# ESP_MainChip.net
KiCad netlist of a schematic drawn in Altium Designer
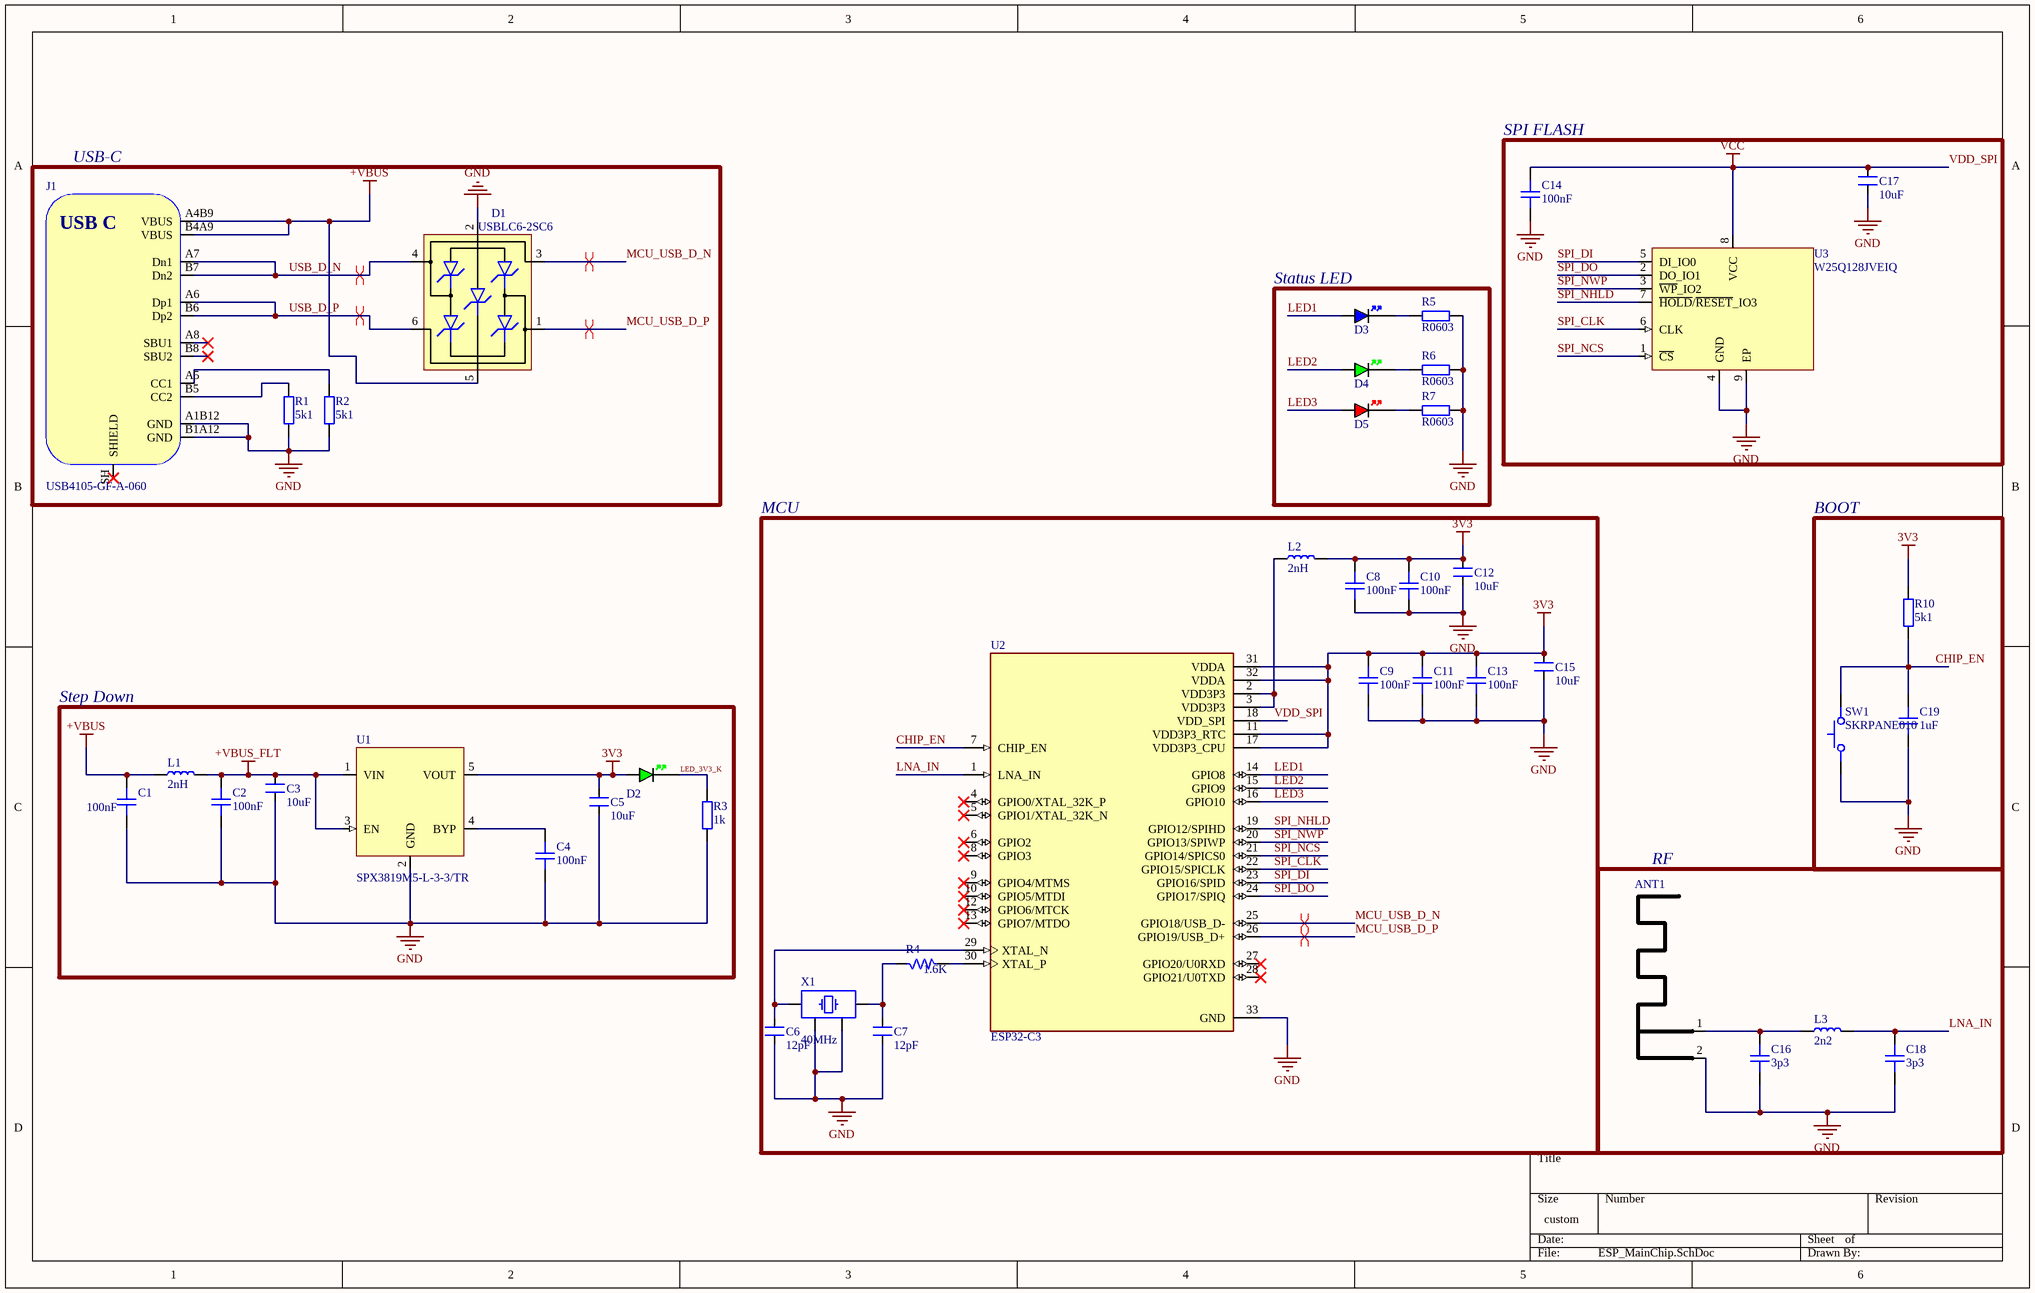
[diagram p0: ESP_MainChip.SchDoc]

(export (version "E")
  (design (tool "Eeschema 10.0.6"))
  (components
    (comp (ref "ANT1")
      (value "PCB Antenna 2.4GHz 50Ohm")
      (footprint "ANT_IFA_USB_2_4GHZ_50R")
      (description "Inverted F 2.4GHz ISM PCB Antenna 50 Ohm")
      (libsource (lib "PMS67") (part "ANT_IFA_USB_2_4GHZ_50R"))
    )
    (comp (ref "C1")
      (value "100nF")
      (footprint "CAP_0603")
      (description "Capacitor SMD 0603")
      (libsource (lib "PMS67") (part "CAP_0603"))
    )
    (comp (ref "C2")
      (value "100nF")
      (footprint "CAP_0603")
      (description "Capacitor SMD 0603")
      (libsource (lib "PMS67") (part "CAP_0603"))
    )
    (comp (ref "C3")
      (value "10uF")
      (footprint "CAP_1206")
      (description "10µF ±10% 50V Ceramic Capacitor X7R 1206 (3216 Metric)")
      (fields
        (field (name "MANUFACTURER") "KEMET")
        (field (name "MANUFACTURER PART NUMBER") "CL31B106KBHNNNE")
      )
      (libsource (lib "ESTEEMPCBLIB") (part "CAP_10uF-50V-10%-1206"))
    )
    (comp (ref "C4")
      (value "100nF")
      (footprint "CAP_0603")
      (description "Capacitor SMD 0603")
      (libsource (lib "PMS67") (part "CAP_0603"))
    )
    (comp (ref "C5")
      (value "10uF")
      (footprint "CAP_1206")
      (description "10µF ±10% 50V Ceramic Capacitor X7R 1206 (3216 Metric)")
      (fields
        (field (name "MANUFACTURER") "KEMET")
        (field (name "MANUFACTURER PART NUMBER") "CL31B106KBHNNNE")
      )
      (libsource (lib "ESTEEMPCBLIB") (part "CAP_10uF-50V-10%-1206"))
    )
    (comp (ref "C6")
      (value "12pF")
      (footprint "CAP_0805")
      (description "12pF ±5% 50V Ceramic Capacitor C0G, NP0 0805 (2012 Metric)")
      (fields
        (field (name "MANUFACTURER") "KEMET")
        (field (name "MANUFACTURER PART NUMBER") "CC0805JRNPO9BN120")
      )
      (libsource (lib "ESTEEMPCBLIB") (part "CAP_12pF-50V-5%-0805"))
    )
    (comp (ref "C7")
      (value "12pF")
      (footprint "CAP_0805")
      (description "12pF ±5% 50V Ceramic Capacitor C0G, NP0 0805 (2012 Metric)")
      (fields
        (field (name "MANUFACTURER") "KEMET")
        (field (name "MANUFACTURER PART NUMBER") "CC0805JRNPO9BN120")
      )
      (libsource (lib "ESTEEMPCBLIB") (part "CAP_12pF-50V-5%-0805"))
    )
    (comp (ref "C8")
      (value "100nF")
      (footprint "CAP_0603")
      (description "Capacitor SMD 0603")
      (libsource (lib "PMS67") (part "CAP_0603"))
    )
    (comp (ref "C9")
      (value "100nF")
      (footprint "CAP_0603")
      (description "Capacitor SMD 0603")
      (libsource (lib "PMS67") (part "CAP_0603"))
    )
    (comp (ref "C10")
      (value "100nF")
      (footprint "CAP_0603")
      (description "Capacitor SMD 0603")
      (libsource (lib "PMS67") (part "CAP_0603"))
    )
    (comp (ref "C11")
      (value "100nF")
      (footprint "CAP_0603")
      (description "Capacitor SMD 0603")
      (libsource (lib "PMS67") (part "CAP_0603"))
    )
    (comp (ref "C12")
      (value "10uF")
      (footprint "CAP_1206")
      (description "10µF ±10% 50V Ceramic Capacitor X7R 1206 (3216 Metric)")
      (fields
        (field (name "MANUFACTURER") "KEMET")
        (field (name "MANUFACTURER PART NUMBER") "CL31B106KBHNNNE")
      )
      (libsource (lib "ESTEEMPCBLIB") (part "CAP_10uF-50V-10%-1206"))
    )
    (comp (ref "C13")
      (value "100nF")
      (footprint "CAP_0603")
      (description "Capacitor SMD 0603")
      (libsource (lib "PMS67") (part "CAP_0603"))
    )
    (comp (ref "C14")
      (value "100nF")
      (footprint "CAP_0603")
      (description "Capacitor SMD 0603")
      (libsource (lib "PMS67") (part "CAP_0603"))
    )
    (comp (ref "C15")
      (value "10uF")
      (footprint "CAP_1206")
      (description "10µF ±10% 50V Ceramic Capacitor X7R 1206 (3216 Metric)")
      (fields
        (field (name "MANUFACTURER") "KEMET")
        (field (name "MANUFACTURER PART NUMBER") "CL31B106KBHNNNE")
      )
      (libsource (lib "ESTEEMPCBLIB") (part "CAP_10uF-50V-10%-1206"))
    )
    (comp (ref "C16")
      (value "3p3")
      (footprint "CAP_0201")
      (description "Capacitor SMD 0201")
      (libsource (lib "PMS67") (part "CAP_0201"))
    )
    (comp (ref "C17")
      (value "10uF")
      (footprint "CAP_1206")
      (description "10µF ±10% 50V Ceramic Capacitor X7R 1206 (3216 Metric)")
      (fields
        (field (name "MANUFACTURER") "KEMET")
        (field (name "MANUFACTURER PART NUMBER") "CL31B106KBHNNNE")
      )
      (libsource (lib "ESTEEMPCBLIB") (part "CAP_10uF-50V-10%-1206"))
    )
    (comp (ref "C18")
      (value "3p3")
      (footprint "CAP_0201")
      (description "Capacitor SMD 0201")
      (libsource (lib "PMS67") (part "CAP_0201"))
    )
    (comp (ref "C19")
      (value "1uF")
      (footprint "CAP_0603")
      (description "Capacitor SMD 0603")
      (libsource (lib "PMS67") (part "CAP_0603"))
    )
    (comp (ref "D1")
      (value "USBLC6-2SC6")
      (footprint "SOT-23-6")
      (description "Low-Capacitance ESD Protection USB")
      (fields (field (name "MANUFACTURER") "STMicroelectronics"))
      (libsource (lib "PMS67") (part "USBLC6-2SC6"))
    )
    (comp (ref "D2")
      (value "GREEN")
      (footprint "LED_0402_GREEN")
      (description "LED 0402 GREEN SMD")
      (libsource (lib "PMS67") (part "LED_0402_GREEN"))
    )
    (comp (ref "D3")
      (value "BLUE")
      (footprint "LED_0402_BLUE")
      (description "LED 0402 BLUE SMD")
      (libsource (lib "PMS67") (part "LED_0402_BLUE"))
    )
    (comp (ref "D4")
      (value "GREEN")
      (footprint "LED_0402_GREEN")
      (description "LED 0402 GREEN SMD")
      (libsource (lib "PMS67") (part "LED_0402_GREEN"))
    )
    (comp (ref "D5")
      (value "RED")
      (footprint "LED_0402_RED")
      (description "LED 0402 RED SMD")
      (libsource (lib "PMS67") (part "LED_0402_RED"))
    )
    (comp (ref "J1")
      (value "USB4105-GF-A-060")
      (footprint "USB4105-GF-A-060")
      (description "USB Connector Type C SMT 12 Pin")
      (fields (field (name "MANUFACTURER") "GCT"))
      (libsource (lib "PMS67") (part "USB4105-GF-A-060"))
    )
    (comp (ref "L1")
      (value "2nH")
      (footprint "IND_0603")
      (description "Inductor SMD 0603")
      (libsource (lib "PMS67") (part "IND_0603"))
    )
    (comp (ref "L2")
      (value "2nH")
      (footprint "IND_0603")
      (description "Inductor SMD 0603")
      (libsource (lib "PMS67") (part "IND_0603"))
    )
    (comp (ref "L3")
      (value "2n2")
      (footprint "IND_1008")
      (description "Inductor SMD 1008")
      (libsource (lib "PMS67") (part "IND_1008"))
    )
    (comp (ref "R1")
      (value "5k1")
      (footprint "RES_0805")
      (description "Resistor SMD 0805")
      (libsource (lib "PMS67") (part "RES_0805"))
    )
    (comp (ref "R2")
      (value "5k1")
      (footprint "RES_0805")
      (description "Resistor SMD 0805")
      (libsource (lib "PMS67") (part "RES_0805"))
    )
    (comp (ref "R3")
      (value "1k")
      (footprint "RES_0603")
      (description "Resistor SMD 0603")
      (libsource (lib "PMS67") (part "RES_0603"))
    )
    (comp (ref "R4")
      (value "1.6K")
      (footprint "RES_0603")
      (description "1.6 kOhms ±1% 0.1W, 1/10W Chip Resistor 0603 (1608 Metric) Thin Film")
      (fields (field (name "MANUFACTURER") "NA"))
      (libsource (lib "ESTEEMPCBLIB") (part "RES_1.6K-0.1W-1%-0603"))
    )
    (comp (ref "R5")
      (value "R0603")
      (footprint "RES_0603")
      (description "Resistor SMD 0603")
      (libsource (lib "PMS67") (part "RES_0603"))
    )
    (comp (ref "R6")
      (value "R0603")
      (footprint "RES_0603")
      (description "Resistor SMD 0603")
      (libsource (lib "PMS67") (part "RES_0603"))
    )
    (comp (ref "R7")
      (value "R0603")
      (footprint "RES_0603")
      (description "Resistor SMD 0603")
      (libsource (lib "PMS67") (part "RES_0603"))
    )
    (comp (ref "R10")
      (value "5k1")
      (footprint "RES_0805")
      (description "Resistor SMD 0805")
      (libsource (lib "PMS67") (part "RES_0805"))
    )
    (comp (ref "SW1")
      (value "SKRPANE010")
      (footprint "SKRPANE010")
      (description "Tactile Switch SMD SPST")
      (fields (field (name "MANUFACTURER") "Alps Alpine"))
      (libsource (lib "PMS67") (part "SKRPANE010"))
    )
    (comp (ref "U1")
      (value "SPX3819M5-L-3-3/TR")
      (footprint "SOT-23-5")
      (description "500mA +3.3V Low-Noise LDO Voltage Regulator")
      (fields (field (name "MANUFACTURER") "MaxLinear"))
      (libsource (lib "PMS67") (part "SPX3819M5-L-3-3/TR"))
    )
    (comp (ref "U2")
      (value "ESP32-C3")
      (footprint "QFN50P500X500X90-33N")
      (fields (field (name "MF") "{'manufacturer': u'Espressif Systems'}"))
      (libsource (lib "SnapEDA_Library") (part "ESP32-C3"))
    )
    (comp (ref "U3")
      (value "W25Q128JVEIQ")
      (footprint "WSON-8-8X6")
      (description "3V 128M-BIT SERIAL FLASH MEMORY WITH DUAL/QUAD SPI & QPI & DTR WSON-8")
      (fields (field (name "MANUFACTURER") "Winbond"))
      (libsource (lib "PMS67") (part "W25Q128JVEIQ"))
    )
    (comp (ref "X1")
      (value "40MHz")
      (footprint "XTAL_2016")
      (description "Crystal SMD 4-Pin 2.0x1.6mm")
      (libsource (lib "PMS67") (part "XTAL_2016"))
    )
  )
  (nets
    (net (code "1") (name "+VBUS") (class "Default")
      (node (ref "C1") (pin "2") (pinfunction "2_2") (pintype "passive"))
      (node (ref "D1") (pin "5") (pinfunction "VBUS_5") (pintype "power_in"))
      (node (ref "J1") (pin "A4B9") (pinfunction "VBUS_A4B9") (pintype "passive"))
      (node (ref "J1") (pin "B4A9") (pinfunction "VBUS_B4A9") (pintype "passive"))
      (node (ref "L1") (pin "1") (pinfunction "1_1") (pintype "passive"))
    )
    (net (code "2") (name "+VBUS_FLT") (class "Default")
      (node (ref "C2") (pin "2") (pinfunction "2_2") (pintype "passive"))
      (node (ref "C3") (pin "2") (pinfunction "2_2") (pintype "passive"))
      (node (ref "L1") (pin "2") (pinfunction "2_2") (pintype "passive"))
      (node (ref "U1") (pin "1") (pinfunction "VIN_1") (pintype "power_in"))
      (node (ref "U1") (pin "3") (pinfunction "EN_3") (pintype "input"))
    )
    (net (code "3") (name "/CHIP_EN") (class "Default")
      (node (ref "C19") (pin "2") (pinfunction "2_2") (pintype "passive"))
      (node (ref "R10") (pin "1") (pinfunction "1_1") (pintype "passive"))
      (node (ref "SW1") (pin "34") (pintype "passive"))
      (node (ref "U2") (pin "7") (pinfunction "CHIP_EN_7") (pintype "input"))
    )
    (net (code "4") (name "/LED1") (class "Default")
      (node (ref "D3") (pin "A") (pinfunction "A_A") (pintype "passive"))
      (node (ref "U2") (pin "14") (pinfunction "GPIO8_14") (pintype "bidirectional"))
    )
    (net (code "5") (name "/LED2") (class "Default")
      (node (ref "D4") (pin "A") (pinfunction "A_A") (pintype "passive"))
      (node (ref "U2") (pin "15") (pinfunction "GPIO9_15") (pintype "bidirectional"))
    )
    (net (code "6") (name "/LED3") (class "Default")
      (node (ref "D5") (pin "A") (pinfunction "A_A") (pintype "passive"))
      (node (ref "U2") (pin "16") (pinfunction "GPIO10_16") (pintype "bidirectional"))
    )
    (net (code "7") (name "/LED_3V3_K") (class "Default")
      (node (ref "D2") (pin "K") (pinfunction "K_K") (pintype "passive"))
      (node (ref "R3") (pin "2") (pinfunction "2_2") (pintype "passive"))
    )
    (net (code "8") (name "/LNA_IN") (class "Default")
      (node (ref "C18") (pin "2") (pinfunction "2_2") (pintype "passive"))
      (node (ref "L3") (pin "2") (pinfunction "2_2") (pintype "passive"))
      (node (ref "U2") (pin "1") (pinfunction "LNA_IN_1") (pintype "input"))
    )
    (net (code "9") (name "/MCU_USB_D_N") (class "Default")
      (node (ref "D1") (pin "3") (pinfunction "IO2_3") (pintype "bidirectional"))
      (node (ref "U2") (pin "25") (pinfunction "GPIO18/USB_D-_25") (pintype "bidirectional"))
    )
    (net (code "10") (name "/MCU_USB_D_P") (class "Default")
      (node (ref "D1") (pin "1") (pinfunction "IO1_1") (pintype "bidirectional"))
      (node (ref "U2") (pin "26") (pinfunction "GPIO19/USB_D+_26") (pintype "bidirectional"))
    )
    (net (code "11") (name "/SPI_CLK") (class "Default")
      (node (ref "U2") (pin "22") (pinfunction "GPIO15/SPICLK_22") (pintype "bidirectional"))
      (node (ref "U3") (pin "6") (pinfunction "CLK_6") (pintype "input"))
    )
    (net (code "12") (name "/SPI_DI") (class "Default")
      (node (ref "U2") (pin "23") (pinfunction "GPIO16/SPID_23") (pintype "bidirectional"))
      (node (ref "U3") (pin "5") (pinfunction "DI_IO0_5") (pintype "bidirectional"))
    )
    (net (code "13") (name "/SPI_DO") (class "Default")
      (node (ref "U2") (pin "24") (pinfunction "GPIO17/SPIQ_24") (pintype "bidirectional"))
      (node (ref "U3") (pin "2") (pinfunction "DO_IO1_2") (pintype "bidirectional"))
    )
    (net (code "14") (name "/SPI_NCS") (class "Default")
      (node (ref "U2") (pin "21") (pinfunction "GPIO14/SPICS0_21") (pintype "bidirectional"))
      (node (ref "U3") (pin "1") (pinfunction "~{CS}_1") (pintype "input"))
    )
    (net (code "15") (name "/SPI_NHLD") (class "Default")
      (node (ref "U2") (pin "19") (pinfunction "GPIO12/SPIHD_19") (pintype "bidirectional"))
      (node (ref "U3") (pin "7") (pinfunction "~{HOLD}/~{RESET}_IO3_7") (pintype "bidirectional"))
    )
    (net (code "16") (name "/SPI_NWP") (class "Default")
      (node (ref "U2") (pin "20") (pinfunction "GPIO13/SPIWP_20") (pintype "bidirectional"))
      (node (ref "U3") (pin "3") (pinfunction "~{WP}_IO2_3") (pintype "bidirectional"))
    )
    (net (code "17") (name "/USB_D_N") (class "Default")
      (node (ref "D1") (pin "4") (pinfunction "IO2_4") (pintype "bidirectional"))
      (node (ref "J1") (pin "A7") (pinfunction "Dn1_A7") (pintype "passive"))
      (node (ref "J1") (pin "B7") (pinfunction "Dn2_B7") (pintype "passive"))
    )
    (net (code "18") (name "/USB_D_P") (class "Default")
      (node (ref "D1") (pin "6") (pinfunction "IO1_6") (pintype "bidirectional"))
      (node (ref "J1") (pin "A6") (pinfunction "Dp1_A6") (pintype "passive"))
      (node (ref "J1") (pin "B6") (pinfunction "Dp2_B6") (pintype "passive"))
    )
    (net (code "19") (name "3V3") (class "Default")
      (node (ref "C10") (pin "2") (pinfunction "2_2") (pintype "passive"))
      (node (ref "C11") (pin "2") (pinfunction "2_2") (pintype "passive"))
      (node (ref "C12") (pin "2") (pinfunction "2_2") (pintype "passive"))
      (node (ref "C13") (pin "2") (pinfunction "2_2") (pintype "passive"))
      (node (ref "C15") (pin "2") (pinfunction "2_2") (pintype "passive"))
      (node (ref "C5") (pin "2") (pinfunction "2_2") (pintype "passive"))
      (node (ref "C8") (pin "2") (pinfunction "2_2") (pintype "passive"))
      (node (ref "C9") (pin "2") (pinfunction "2_2") (pintype "passive"))
      (node (ref "D2") (pin "A") (pinfunction "A_A") (pintype "passive"))
      (node (ref "L2") (pin "2") (pinfunction "2_2") (pintype "passive"))
      (node (ref "R10") (pin "2") (pinfunction "2_2") (pintype "passive"))
      (node (ref "U1") (pin "5") (pinfunction "VOUT_5") (pintype "power_in"))
      (node (ref "U2") (pin "11") (pinfunction "VDD3P3_RTC_11") (pintype "power_in"))
      (node (ref "U2") (pin "17") (pinfunction "VDD3P3_CPU_17") (pintype "power_in"))
      (node (ref "U2") (pin "31") (pinfunction "VDDA_31") (pintype "power_in"))
      (node (ref "U2") (pin "32") (pinfunction "VDDA_32") (pintype "power_in"))
    )
    (net (code "20") (name "GND") (class "Default")
      (node (ref "ANT1") (pin "2") (pinfunction "GND_2") (pintype "passive"))
      (node (ref "C1") (pin "1") (pinfunction "1_1") (pintype "passive"))
      (node (ref "C10") (pin "1") (pinfunction "1_1") (pintype "passive"))
      (node (ref "C11") (pin "1") (pinfunction "1_1") (pintype "passive"))
      (node (ref "C12") (pin "1") (pinfunction "1_1") (pintype "passive"))
      (node (ref "C13") (pin "1") (pinfunction "1_1") (pintype "passive"))
      (node (ref "C14") (pin "1") (pinfunction "1_1") (pintype "passive"))
      (node (ref "C15") (pin "1") (pinfunction "1_1") (pintype "passive"))
      (node (ref "C16") (pin "1") (pinfunction "1_1") (pintype "passive"))
      (node (ref "C17") (pin "1") (pinfunction "1_1") (pintype "passive"))
      (node (ref "C18") (pin "1") (pinfunction "1_1") (pintype "passive"))
      (node (ref "C19") (pin "1") (pinfunction "1_1") (pintype "passive"))
      (node (ref "C2") (pin "1") (pinfunction "1_1") (pintype "passive"))
      (node (ref "C3") (pin "1") (pinfunction "1_1") (pintype "passive"))
      (node (ref "C4") (pin "1") (pinfunction "1_1") (pintype "passive"))
      (node (ref "C5") (pin "1") (pinfunction "1_1") (pintype "passive"))
      (node (ref "C6") (pin "1") (pinfunction "1_1") (pintype "passive"))
      (node (ref "C7") (pin "1") (pinfunction "1_1") (pintype "passive"))
      (node (ref "C8") (pin "1") (pinfunction "1_1") (pintype "passive"))
      (node (ref "C9") (pin "1") (pinfunction "1_1") (pintype "passive"))
      (node (ref "D1") (pin "2") (pinfunction "GND_2") (pintype "power_in"))
      (node (ref "J1") (pin "A1B12") (pinfunction "GND_A1B12") (pintype "passive"))
      (node (ref "J1") (pin "B1A12") (pinfunction "GND_B1A12") (pintype "passive"))
      (node (ref "R1") (pin "1") (pinfunction "1_1") (pintype "passive"))
      (node (ref "R2") (pin "1") (pinfunction "1_1") (pintype "passive"))
      (node (ref "R3") (pin "1") (pinfunction "1_1") (pintype "passive"))
      (node (ref "R5") (pin "1") (pinfunction "1_1") (pintype "passive"))
      (node (ref "R6") (pin "1") (pinfunction "1_1") (pintype "passive"))
      (node (ref "R7") (pin "1") (pinfunction "1_1") (pintype "passive"))
      (node (ref "SW1") (pin "12") (pintype "passive"))
      (node (ref "U1") (pin "2") (pinfunction "GND_2") (pintype "power_in"))
      (node (ref "U2") (pin "33") (pinfunction "GND_33") (pintype "power_in"))
      (node (ref "U3") (pin "4") (pinfunction "GND_4") (pintype "power_in"))
      (node (ref "U3") (pin "9") (pinfunction "EP_9") (pintype "power_in"))
      (node (ref "X1") (pin "2") (pinfunction "2_2") (pintype "passive"))
      (node (ref "X1") (pin "4") (pinfunction "4_4") (pintype "passive"))
    )
    (net (code "21") (name "Net-(ANT1-RF)") (class "Default")
      (node (ref "ANT1") (pin "1") (pinfunction "RF_1") (pintype "passive"))
      (node (ref "C16") (pin "2") (pinfunction "2_2") (pintype "passive"))
      (node (ref "L3") (pin "1") (pinfunction "1_1") (pintype "passive"))
    )
    (net (code "22") (name "Net-(C7-Pad2)") (class "Default")
      (node (ref "C7") (pin "2") (pinfunction "2_2") (pintype "passive"))
      (node (ref "R4") (pin "1") (pinfunction "1_1") (pintype "passive"))
      (node (ref "X1") (pin "3") (pinfunction "3_3") (pintype "passive"))
    )
    (net (code "23") (name "Net-(D3-PadK)") (class "Default")
      (node (ref "D3") (pin "K") (pinfunction "K_K") (pintype "passive"))
      (node (ref "R5") (pin "2") (pinfunction "2_2") (pintype "passive"))
    )
    (net (code "24") (name "Net-(D4-PadK)") (class "Default")
      (node (ref "D4") (pin "K") (pinfunction "K_K") (pintype "passive"))
      (node (ref "R6") (pin "2") (pinfunction "2_2") (pintype "passive"))
    )
    (net (code "25") (name "Net-(D5-PadK)") (class "Default")
      (node (ref "D5") (pin "K") (pinfunction "K_K") (pintype "passive"))
      (node (ref "R7") (pin "2") (pinfunction "2_2") (pintype "passive"))
    )
    (net (code "26") (name "Net-(J1-CC1)") (class "Default")
      (node (ref "J1") (pin "A5") (pinfunction "CC1_A5") (pintype "passive"))
      (node (ref "R2") (pin "2") (pinfunction "2_2") (pintype "passive"))
    )
    (net (code "27") (name "Net-(J1-CC2)") (class "Default")
      (node (ref "J1") (pin "B5") (pinfunction "CC2_B5") (pintype "passive"))
      (node (ref "R1") (pin "2") (pinfunction "2_2") (pintype "passive"))
    )
    (net (code "28") (name "Net-(L2-Pad1)") (class "Default")
      (node (ref "L2") (pin "1") (pinfunction "1_1") (pintype "passive"))
      (node (ref "U2") (pin "2") (pinfunction "VDD3P3_2") (pintype "power_in"))
      (node (ref "U2") (pin "3") (pinfunction "VDD3P3_3") (pintype "power_in"))
    )
    (net (code "29") (name "Net-(U1-BYP)") (class "Default")
      (node (ref "C4") (pin "2") (pinfunction "2_2") (pintype "passive"))
      (node (ref "U1") (pin "4") (pinfunction "BYP_4") (pintype "passive"))
    )
    (net (code "30") (name "Net-(U2-XTAL_N)") (class "Default")
      (node (ref "C6") (pin "2") (pinfunction "2_2") (pintype "passive"))
      (node (ref "U2") (pin "29") (pinfunction "XTAL_N_29") (pintype "input"))
      (node (ref "X1") (pin "1") (pinfunction "1_1") (pintype "passive"))
    )
    (net (code "31") (name "Net-(U2-XTAL_P)") (class "Default")
      (node (ref "R4") (pin "2") (pinfunction "2_2") (pintype "passive"))
      (node (ref "U2") (pin "30") (pinfunction "XTAL_P_30") (pintype "input"))
    )
    (net (code "32") (name "VCC") (class "Default")
      (node (ref "C14") (pin "2") (pinfunction "2_2") (pintype "passive"))
      (node (ref "C17") (pin "2") (pinfunction "2_2") (pintype "passive"))
      (node (ref "U2") (pin "18") (pinfunction "VDD_SPI_18") (pintype "power_in"))
      (node (ref "U3") (pin "8") (pinfunction "VCC_8") (pintype "power_in"))
    )
    (net (code "33") (name "unconnected-(J1-SBU1-PadA8)") (class "Default")
      (node (ref "J1") (pin "A8") (pinfunction "SBU1_A8") (pintype "passive+no_connect"))
    )
    (net (code "34") (name "unconnected-(J1-SBU2-PadB8)") (class "Default")
      (node (ref "J1") (pin "B8") (pinfunction "SBU2_B8") (pintype "passive+no_connect"))
    )
    (net (code "35") (name "unconnected-(J1-SHIELD-PadSH)") (class "Default")
      (node (ref "J1") (pin "SH") (pinfunction "SHIELD_SH") (pintype "passive+no_connect"))
    )
    (net (code "36") (name "unconnected-(U2-GPIO0{slash}XTAL_32K_P-Pad4)") (class "Default")
      (node (ref "U2") (pin "4") (pinfunction "GPIO0/XTAL_32K_P_4") (pintype "bidirectional+no_connect"))
    )
    (net (code "37") (name "unconnected-(U2-GPIO1{slash}XTAL_32K_N-Pad5)") (class "Default")
      (node (ref "U2") (pin "5") (pinfunction "GPIO1/XTAL_32K_N_5") (pintype "bidirectional+no_connect"))
    )
    (net (code "38") (name "unconnected-(U2-GPIO2-Pad6)") (class "Default")
      (node (ref "U2") (pin "6") (pinfunction "GPIO2_6") (pintype "bidirectional+no_connect"))
    )
    (net (code "39") (name "unconnected-(U2-GPIO3-Pad8)") (class "Default")
      (node (ref "U2") (pin "8") (pinfunction "GPIO3_8") (pintype "bidirectional+no_connect"))
    )
    (net (code "40") (name "unconnected-(U2-GPIO4{slash}MTMS-Pad9)") (class "Default")
      (node (ref "U2") (pin "9") (pinfunction "GPIO4/MTMS_9") (pintype "bidirectional+no_connect"))
    )
    (net (code "41") (name "unconnected-(U2-GPIO5{slash}MTDI-Pad10)") (class "Default")
      (node (ref "U2") (pin "10") (pinfunction "GPIO5/MTDI_10") (pintype "bidirectional+no_connect"))
    )
    (net (code "42") (name "unconnected-(U2-GPIO6{slash}MTCK-Pad12)") (class "Default")
      (node (ref "U2") (pin "12") (pinfunction "GPIO6/MTCK_12") (pintype "bidirectional+no_connect"))
    )
    (net (code "43") (name "unconnected-(U2-GPIO7{slash}MTDO-Pad13)") (class "Default")
      (node (ref "U2") (pin "13") (pinfunction "GPIO7/MTDO_13") (pintype "bidirectional+no_connect"))
    )
    (net (code "44") (name "unconnected-(U2-GPIO20{slash}U0RXD-Pad27)") (class "Default")
      (node (ref "U2") (pin "27") (pinfunction "GPIO20/U0RXD_27") (pintype "bidirectional+no_connect"))
    )
    (net (code "45") (name "unconnected-(U2-GPIO21{slash}U0TXD-Pad28)") (class "Default")
      (node (ref "U2") (pin "28") (pinfunction "GPIO21/U0TXD_28") (pintype "bidirectional+no_connect"))
    )
  )
)
